# AUTOPILOT_IO.net
KiCad netlist of a schematic drawn in EAGLE
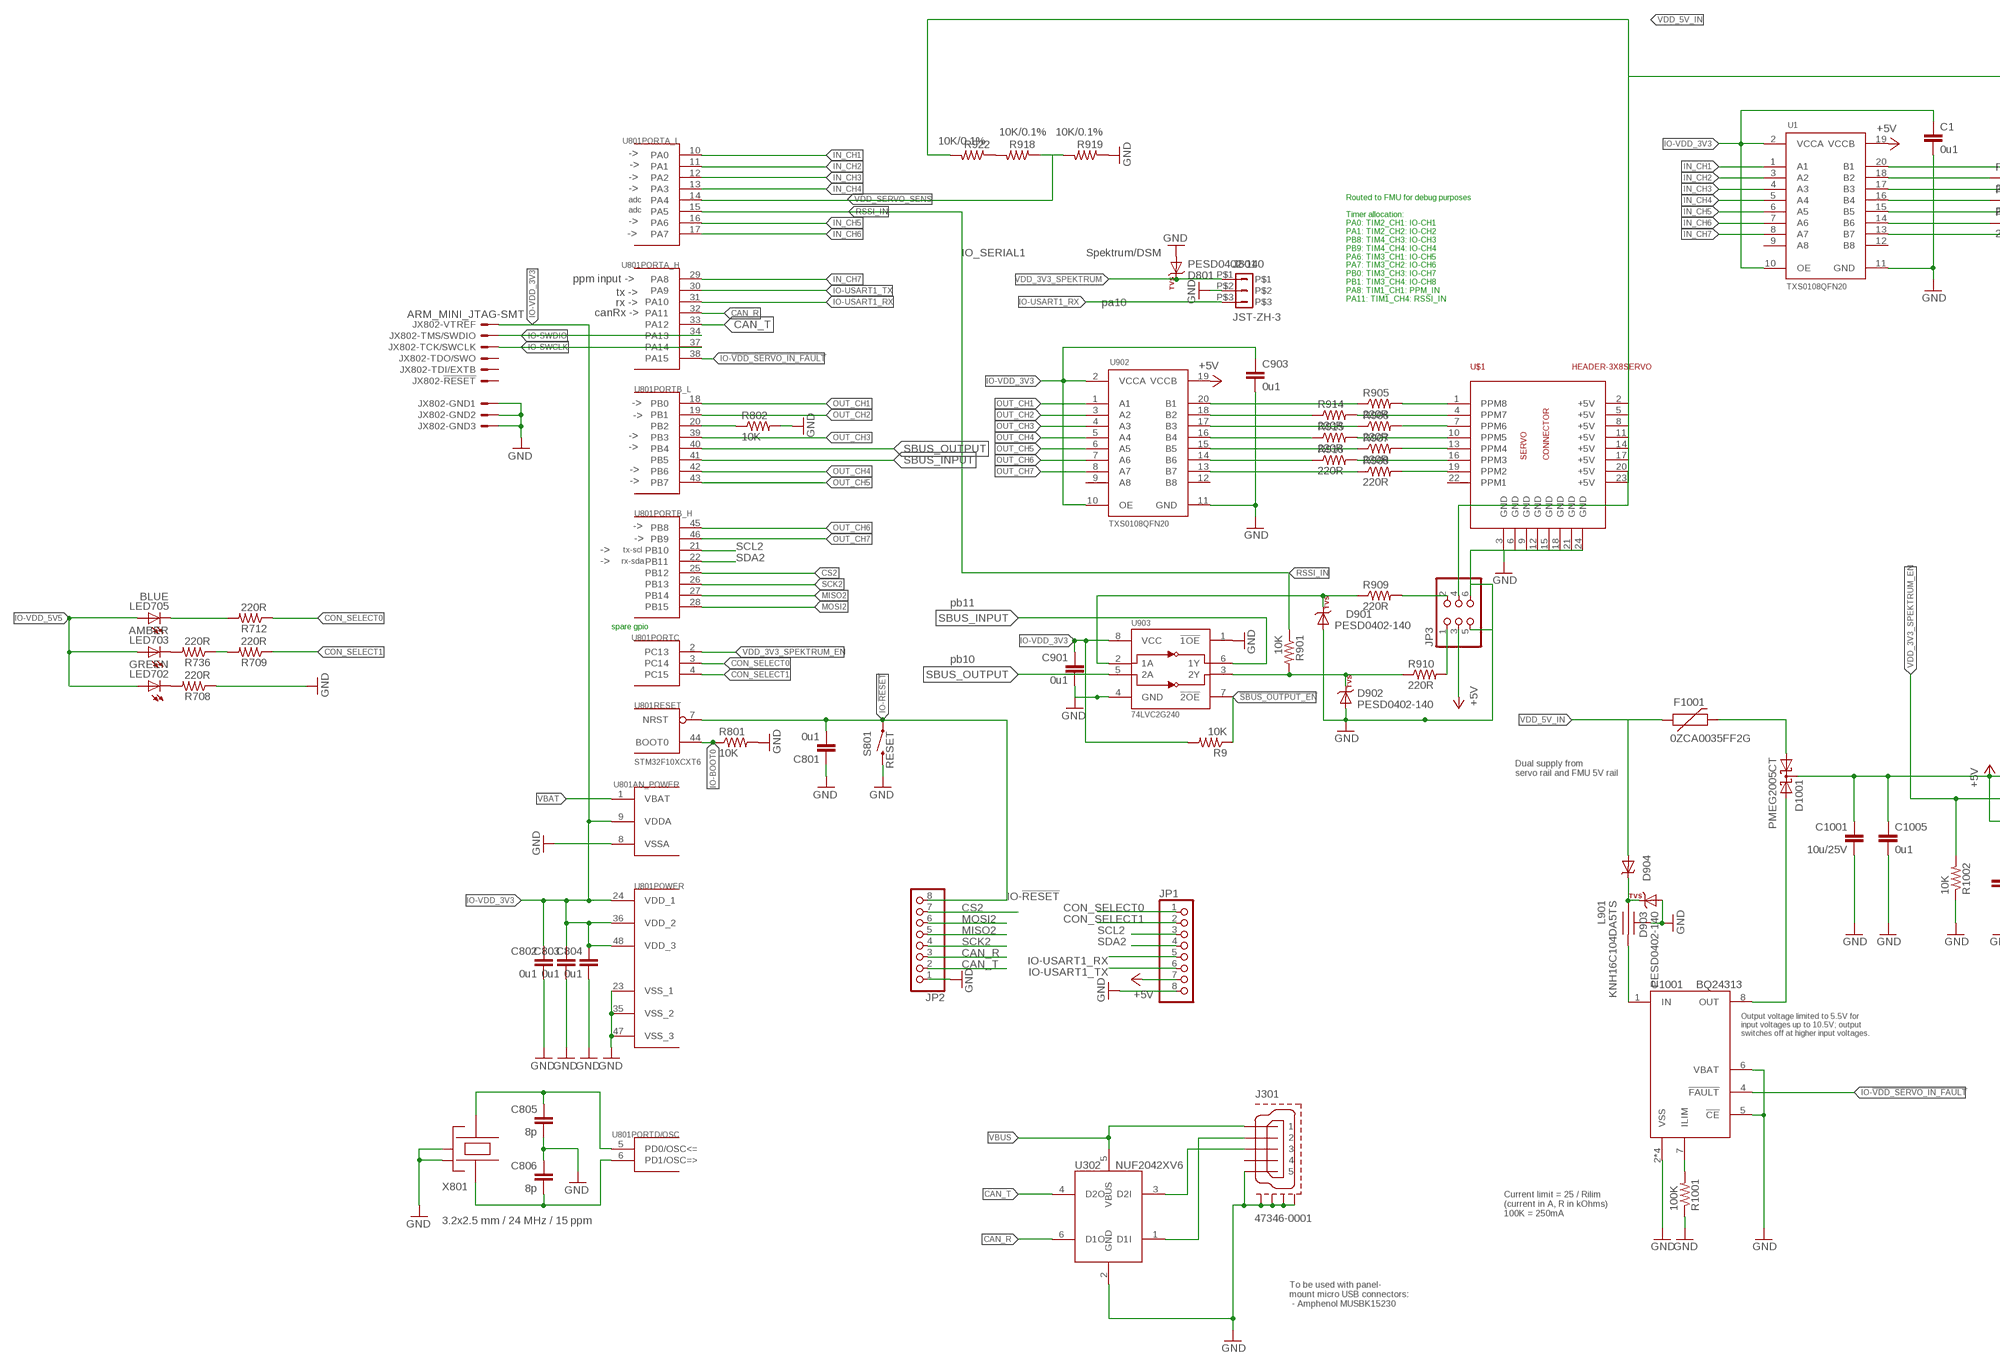
[diagram p0: schematic, sheet 1, part 1 of 2]
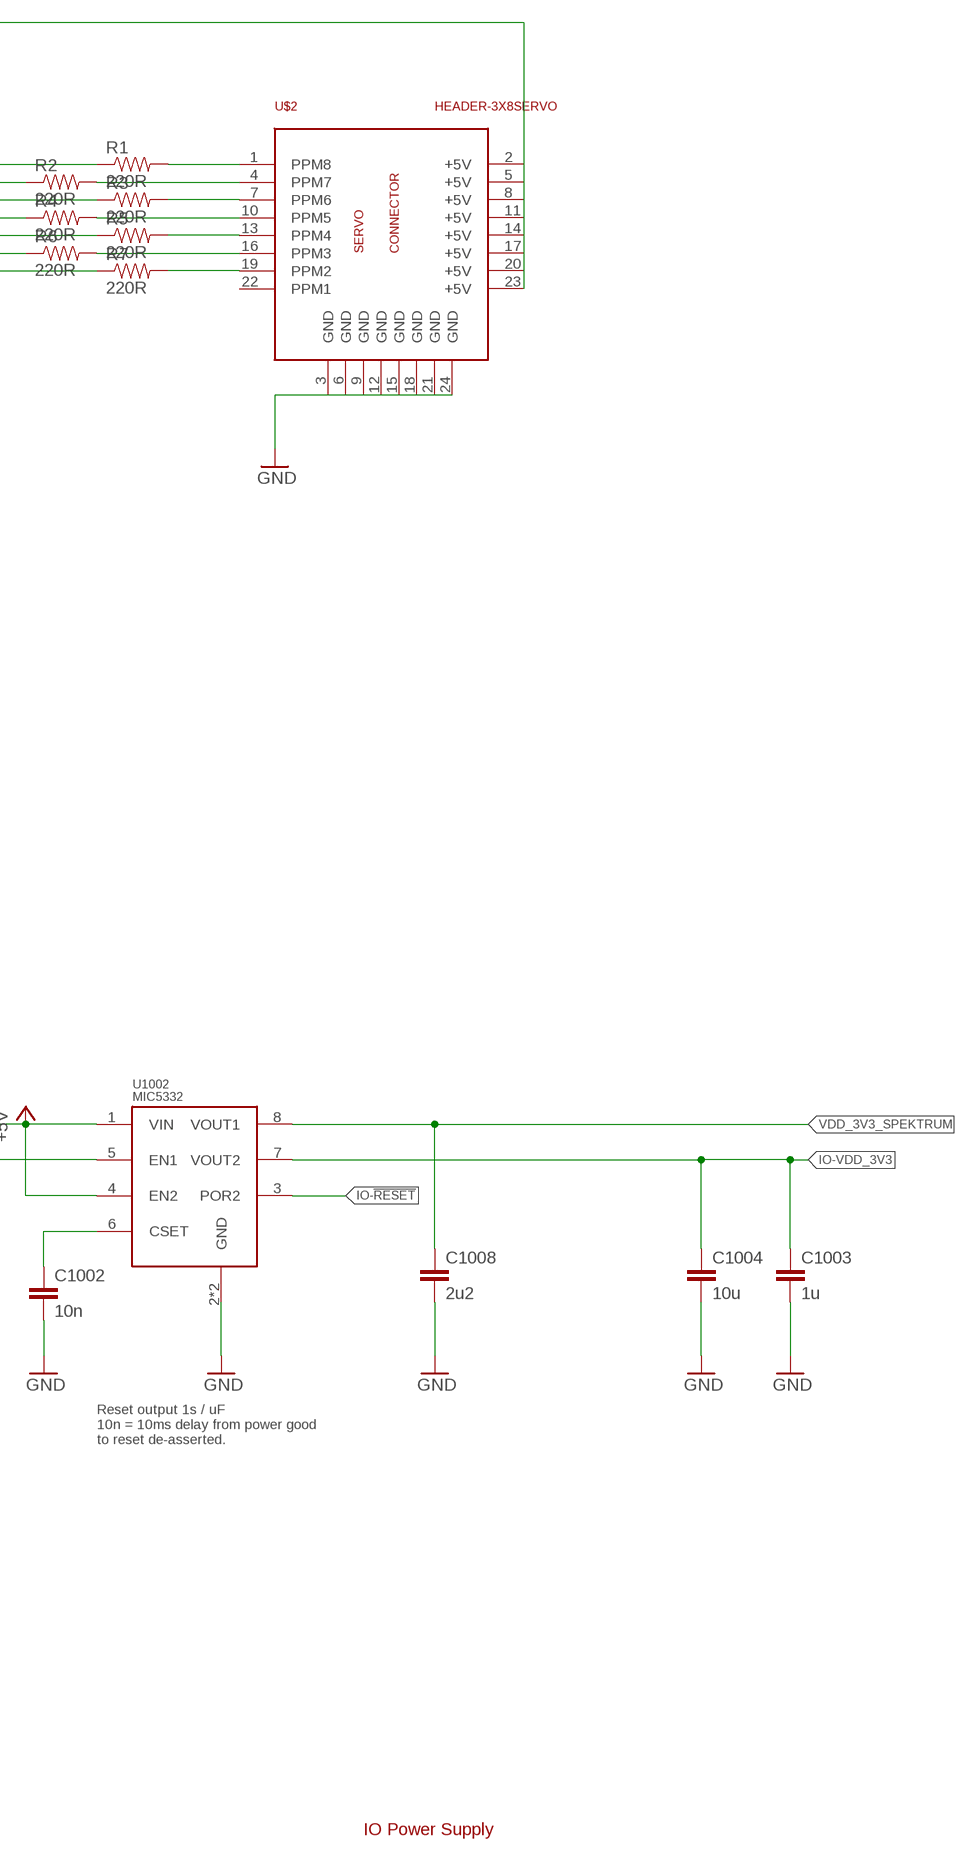
[diagram p1: schematic, sheet 1, part 2 of 2]

(export (version "E")
  (design (tool "Eeschema 10.0.6"))
  (components
    (comp (ref "C1")
      (value "0u1")
      (footprint "eagle-import:0402-CAP")
      (fields (field (name "PARTNO") "CC0402ZRY5V7BB104"))
      (libsource (lib "eagle-import") (part "CAP0402"))
    )
    (comp (ref "C801")
      (value "0u1")
      (footprint "eagle-import:0402-CAP")
      (fields (field (name "PARTNO") "CC0402ZRY5V7BB104"))
      (libsource (lib "eagle-import") (part "CAP0402"))
    )
    (comp (ref "C802")
      (value "0u1")
      (footprint "eagle-import:0402-CAP")
      (fields (field (name "PARTNO") "CC0402ZRY5V7BB104"))
      (libsource (lib "eagle-import") (part "CAP0402"))
    )
    (comp (ref "C803")
      (value "0u1")
      (footprint "eagle-import:0402-CAP")
      (fields (field (name "PARTNO") "CC0402ZRY5V7BB104"))
      (libsource (lib "eagle-import") (part "CAP0402"))
    )
    (comp (ref "C804")
      (value "0u1")
      (footprint "eagle-import:0402-CAP")
      (fields (field (name "PARTNO") "CC0402ZRY5V7BB104"))
      (libsource (lib "eagle-import") (part "CAP0402"))
    )
    (comp (ref "C805")
      (value "8p")
      (footprint "eagle-import:0402-CAP")
      (fields (field (name "PARTNO") "C1005C0G1H080C"))
      (libsource (lib "eagle-import") (part "CAP0402"))
    )
    (comp (ref "C806")
      (value "8p")
      (footprint "eagle-import:0402-CAP")
      (fields (field (name "PARTNO") "C1005C0G1H080C"))
      (libsource (lib "eagle-import") (part "CAP0402"))
    )
    (comp (ref "C901")
      (value "0u1")
      (footprint "eagle-import:0402-CAP")
      (fields (field (name "PARTNO") "CC0402ZRY5V7BB104"))
      (libsource (lib "eagle-import") (part "CAP0402"))
    )
    (comp (ref "C903")
      (value "0u1")
      (footprint "eagle-import:0402-CAP")
      (fields (field (name "PARTNO") "CC0402ZRY5V7BB104"))
      (libsource (lib "eagle-import") (part "CAP0402"))
    )
    (comp (ref "C1001")
      (value "10u/25V")
      (footprint "eagle-import:0805-CAP")
      (fields (field (name "PARTNO") "CL21A106KAYNNNE"))
      (libsource (lib "eagle-import") (part "CAP0805"))
    )
    (comp (ref "C1002")
      (value "10n")
      (footprint "eagle-import:0402-CAP")
      (fields (field (name "PARTNO") "CC0402KRX7R7BB103"))
      (libsource (lib "eagle-import") (part "CAP0402"))
    )
    (comp (ref "C1003")
      (value "1u")
      (footprint "eagle-import:0603-CAP")
      (fields (field (name "PARTNO") "CC0603ZRY5V7BB105"))
      (libsource (lib "eagle-import") (part "CAP0603"))
    )
    (comp (ref "C1004")
      (value "10u")
      (footprint "eagle-import:0603-CAP")
      (fields (field (name "PARTNO") "C1608X5R1A106K080AC"))
      (libsource (lib "eagle-import") (part "CAP0603"))
    )
    (comp (ref "C1005")
      (value "0u1")
      (footprint "eagle-import:0402-CAP")
      (fields (field (name "PARTNO") "CC0402ZRY5V7BB104"))
      (libsource (lib "eagle-import") (part "CAP0402"))
    )
    (comp (ref "C1008")
      (value "2u2")
      (footprint "eagle-import:0402-CAP")
      (fields (field (name "PARTNO") "C1005X6S1C225K050BC"))
      (libsource (lib "eagle-import") (part "CAP0402"))
    )
    (comp (ref "D801")
      (value "PESD0402-140")
      (footprint "eagle-import:0402-TVS")
      (libsource (lib "eagle-import") (part "DIODE-TVS"))
    )
    (comp (ref "D901")
      (value "PESD0402-140")
      (footprint "eagle-import:0402-TVS")
      (libsource (lib "eagle-import") (part "DIODE-TVS"))
    )
    (comp (ref "D902")
      (value "PESD0402-140")
      (footprint "eagle-import:0402-TVS")
      (libsource (lib "eagle-import") (part "DIODE-TVS"))
    )
    (comp (ref "D903")
      (value "PESD0402-140")
      (footprint "eagle-import:0402-TVS")
      (libsource (lib "eagle-import") (part "DIODE-TVS"))
    )
    (comp (ref "D904")
      (value "MSS1P4-M3")
      (footprint "eagle-import:MICROSMP")
      (fields (field (name "PARTNO") "MSS1P4-M3/89A"))
      (libsource (lib "eagle-import") (part "DIODE-SCHOTTKY_MSMP"))
    )
    (comp (ref "D1001")
      (value "PMEG2005CT")
      (footprint "eagle-import:SOT23-3")
      (libsource (lib "eagle-import") (part "PMEG2005CT"))
    )
    (comp (ref "F1001")
      (value "0ZCA0035FF2G")
      (footprint "eagle-import:PTC-1206")
      (libsource (lib "eagle-import") (part "PTCSMD"))
    )
    (comp (ref "J301")
      (value "47346-0001")
      (footprint "eagle-import:MOLEX-47346-0001")
      (libsource (lib "eagle-import") (part "MOLEX-47346-0001"))
    )
    (comp (ref "J801")
      (value "JST-ZH-3")
      (footprint "eagle-import:JST-ZH-SMT-VERTICAL")
      (fields (field (name "PARTNO") "B3B-ZR-SM4-TF (LF)(SN)(P)"))
      (libsource (lib "eagle-import") (part "JST-ZH-3"))
    )
    (comp (ref "JP1")
      (value "PINHD-1X8")
      (footprint "eagle-import:1X08")
      (libsource (lib "eagle-import") (part "PINHD-1X8"))
    )
    (comp (ref "JP2")
      (value "PINHD-1X8")
      (footprint "eagle-import:1X08")
      (libsource (lib "eagle-import") (part "PINHD-1X8"))
    )
    (comp (ref "JP3")
      (value "PINHD-2X3")
      (footprint "eagle-import:2X03")
      (libsource (lib "eagle-import") (part "PINHD-2X3"))
    )
    (comp (ref "JX802")
      (value "ARM_MINI_JTAG-SMT")
      (footprint "eagle-import:FTSH-105-01-XXX-DV-K")
      (fields (field (name "BOM") "EXCLUDE") (field (name "PARTNO") "M50-3900542"))
      (libsource (lib "eagle-import") (part "ARM_MINI_JTAG-SMT"))
    )
    (comp (ref "L901")
      (value "KNH16C104DA5TS")
      (footprint "eagle-import:KYOCERA-KNH16-DA")
      (libsource (lib "eagle-import") (part "KNH16C104DA5TS"))
    )
    (comp (ref "LED702")
      (value "GREEN")
      (footprint "eagle-import:0603-LED")
      (fields (field (name "PARTNO") "APTD1608CGCK"))
      (libsource (lib "eagle-import") (part "LED0603"))
    )
    (comp (ref "LED703")
      (value "AMBER")
      (footprint "eagle-import:0603-LED")
      (fields (field (name "PARTNO") "APTD1608SECK"))
      (libsource (lib "eagle-import") (part "LED0603"))
    )
    (comp (ref "LED705")
      (value "BLUE")
      (footprint "eagle-import:0603-LED")
      (fields (field (name "PARTNO") "APTD1608QBC/D"))
      (libsource (lib "eagle-import") (part "LED0603"))
    )
    (comp (ref "R1")
      (value "220R")
      (footprint "eagle-import:0402-RES")
      (fields (field (name "PARTNO") "RC0402FR-07220RL"))
      (libsource (lib "eagle-import") (part "RESISTOR0402-RES"))
    )
    (comp (ref "R2")
      (value "220R")
      (footprint "eagle-import:0402-RES")
      (fields (field (name "PARTNO") "RC0402FR-07220RL"))
      (libsource (lib "eagle-import") (part "RESISTOR0402-RES"))
    )
    (comp (ref "R3")
      (value "220R")
      (footprint "eagle-import:0402-RES")
      (fields (field (name "PARTNO") "RC0402FR-07220RL"))
      (libsource (lib "eagle-import") (part "RESISTOR0402-RES"))
    )
    (comp (ref "R4")
      (value "220R")
      (footprint "eagle-import:0402-RES")
      (fields (field (name "PARTNO") "RC0402FR-07220RL"))
      (libsource (lib "eagle-import") (part "RESISTOR0402-RES"))
    )
    (comp (ref "R5")
      (value "220R")
      (footprint "eagle-import:0402-RES")
      (fields (field (name "PARTNO") "RC0402FR-07220RL"))
      (libsource (lib "eagle-import") (part "RESISTOR0402-RES"))
    )
    (comp (ref "R6")
      (value "220R")
      (footprint "eagle-import:0402-RES")
      (fields (field (name "PARTNO") "RC0402FR-07220RL"))
      (libsource (lib "eagle-import") (part "RESISTOR0402-RES"))
    )
    (comp (ref "R7")
      (value "220R")
      (footprint "eagle-import:0402-RES")
      (fields (field (name "PARTNO") "RC0402FR-07220RL"))
      (libsource (lib "eagle-import") (part "RESISTOR0402-RES"))
    )
    (comp (ref "R9")
      (value "10K")
      (footprint "eagle-import:0402-RES")
      (fields (field (name "PARTNO") "RC0402FR-0710KL"))
      (libsource (lib "eagle-import") (part "RESISTOR0402-RES"))
    )
    (comp (ref "R708")
      (value "220R")
      (footprint "eagle-import:0402-RES")
      (fields (field (name "PARTNO") "RC0402FR-07220RL"))
      (libsource (lib "eagle-import") (part "RESISTOR0402-RES"))
    )
    (comp (ref "R709")
      (value "220R")
      (footprint "eagle-import:0402-RES")
      (fields (field (name "PARTNO") "RC0402FR-07220RL"))
      (libsource (lib "eagle-import") (part "RESISTOR0402-RES"))
    )
    (comp (ref "R712")
      (value "220R")
      (footprint "eagle-import:0402-RES")
      (fields (field (name "PARTNO") "RC0402FR-07220RL"))
      (libsource (lib "eagle-import") (part "RESISTOR0402-RES"))
    )
    (comp (ref "R736")
      (value "220R")
      (footprint "eagle-import:0402-RES")
      (fields (field (name "PARTNO") "RC0402FR-07220RL"))
      (libsource (lib "eagle-import") (part "RESISTOR0402-RES"))
    )
    (comp (ref "R801")
      (value "10K")
      (footprint "eagle-import:0402-RES")
      (fields (field (name "PARTNO") "RC0402FR-0710KL"))
      (libsource (lib "eagle-import") (part "RESISTOR0402-RES"))
    )
    (comp (ref "R802")
      (value "10K")
      (footprint "eagle-import:0402-RES")
      (fields (field (name "PARTNO") "RC0402FR-0710KL"))
      (libsource (lib "eagle-import") (part "RESISTOR0402-RES"))
    )
    (comp (ref "R901")
      (value "10K")
      (footprint "eagle-import:0402-RES")
      (fields (field (name "PARTNO") "RC0402FR-0710KL"))
      (libsource (lib "eagle-import") (part "RESISTOR0402-RES"))
    )
    (comp (ref "R905")
      (value "220R")
      (footprint "eagle-import:0402-RES")
      (fields (field (name "PARTNO") "RC0402FR-07220RL"))
      (libsource (lib "eagle-import") (part "RESISTOR0402-RES"))
    )
    (comp (ref "R906")
      (value "220R")
      (footprint "eagle-import:0402-RES")
      (fields (field (name "PARTNO") "RC0402FR-07220RL"))
      (libsource (lib "eagle-import") (part "RESISTOR0402-RES"))
    )
    (comp (ref "R907")
      (value "220R")
      (footprint "eagle-import:0402-RES")
      (fields (field (name "PARTNO") "RC0402FR-07220RL"))
      (libsource (lib "eagle-import") (part "RESISTOR0402-RES"))
    )
    (comp (ref "R908")
      (value "220R")
      (footprint "eagle-import:0402-RES")
      (fields (field (name "PARTNO") "RC0402FR-07220RL"))
      (libsource (lib "eagle-import") (part "RESISTOR0402-RES"))
    )
    (comp (ref "R909")
      (value "220R")
      (footprint "eagle-import:0402-RES")
      (fields (field (name "PARTNO") "RC0402FR-07220RL"))
      (libsource (lib "eagle-import") (part "RESISTOR0402-RES"))
    )
    (comp (ref "R910")
      (value "220R")
      (footprint "eagle-import:0402-RES")
      (fields (field (name "PARTNO") "RC0402FR-07220RL"))
      (libsource (lib "eagle-import") (part "RESISTOR0402-RES"))
    )
    (comp (ref "R914")
      (value "220R")
      (footprint "eagle-import:0402-RES")
      (fields (field (name "PARTNO") "RC0402FR-07220RL"))
      (libsource (lib "eagle-import") (part "RESISTOR0402-RES"))
    )
    (comp (ref "R915")
      (value "220R")
      (footprint "eagle-import:0402-RES")
      (fields (field (name "PARTNO") "RC0402FR-07220RL"))
      (libsource (lib "eagle-import") (part "RESISTOR0402-RES"))
    )
    (comp (ref "R916")
      (value "220R")
      (footprint "eagle-import:0402-RES")
      (fields (field (name "PARTNO") "RC0402FR-07220RL"))
      (libsource (lib "eagle-import") (part "RESISTOR0402-RES"))
    )
    (comp (ref "R918")
      (value "10K/0.1%")
      (footprint "eagle-import:0402-RES")
      (fields (field (name "PARTNO") "ERA-2AEB103X"))
      (libsource (lib "eagle-import") (part "RESISTOR0402-RES"))
    )
    (comp (ref "R919")
      (value "10K/0.1%")
      (footprint "eagle-import:0402-RES")
      (fields (field (name "PARTNO") "ERA-2AEB103X"))
      (libsource (lib "eagle-import") (part "RESISTOR0402-RES"))
    )
    (comp (ref "R922")
      (value "10K/0.1%")
      (footprint "eagle-import:0402-RES")
      (fields (field (name "PARTNO") "ERA-2AEB103X"))
      (libsource (lib "eagle-import") (part "RESISTOR0402-RES"))
    )
    (comp (ref "R1001")
      (value "100K")
      (footprint "eagle-import:0402-RES")
      (fields (field (name "PARTNO") "RC0402FR-07100KL"))
      (libsource (lib "eagle-import") (part "RESISTOR0402-RES"))
    )
    (comp (ref "R1002")
      (value "10K")
      (footprint "eagle-import:0402-RES")
      (fields (field (name "PARTNO") "RC0402FR-0710KL"))
      (libsource (lib "eagle-import") (part "RESISTOR0402-RES"))
    )
    (comp (ref "S801")
      (value "RESET")
      (footprint "eagle-import:EVQP7J01K")
      (fields (field (name "PARTNO") "EVQ-P7J01P"))
      (libsource (lib "eagle-import") (part "SWITCH-MOMENTARY-2"))
    )
    (comp (ref "U$1")
      (value "HEADER-3X8SERVO")
      (footprint "eagle-import:3X8RA")
      (libsource (lib "eagle-import") (part "HEADER-3X8SERVO"))
    )
    (comp (ref "U$2")
      (value "HEADER-3X8SERVO")
      (footprint "eagle-import:3X8RA")
      (libsource (lib "eagle-import") (part "HEADER-3X8SERVO"))
    )
    (comp (ref "U1")
      (value "TXS0108QFN20")
      (footprint "eagle-import:QFN20-RGY")
      (fields (field (name "PARTNO") "TXS0108ERGYR"))
      (libsource (lib "eagle-import") (part "TXS0108QFN20"))
    )
    (comp (ref "U302")
      (value "NUF2042XV6")
      (footprint "eagle-import:SOT563-6")
      (fields (field (name "PARTNO") "NUF2042XV6T1G"))
      (libsource (lib "eagle-import") (part "NUF2042XV6"))
    )
    (comp (ref "U801")
      (value "STM32F10XCXT6")
      (footprint "eagle-import:TQFP48")
      (fields (field (name "PARTNO") "STM32F100C8T6B"))
      (libsource (lib "eagle-import") (part "STM32F10XCXT6"))
    )
    (comp (ref "U902")
      (value "TXS0108QFN20")
      (footprint "eagle-import:QFN20-RGY")
      (fields (field (name "PARTNO") "TXS0108ERGYR"))
      (libsource (lib "eagle-import") (part "TXS0108QFN20"))
    )
    (comp (ref "U903")
      (value "74LVC2G240")
      (footprint "eagle-import:TSSOP8_SOT505-2")
      (fields (field (name "PARTNO") "74LVC2G240DP,125"))
      (libsource (lib "eagle-import") (part "74LVC2G240-TSSOP-8"))
    )
    (comp (ref "U1001")
      (value "BQ24313")
      (footprint "eagle-import:QFN8-DSG")
      (fields (field (name "PARTNO") "BQ24313DSGT"))
      (libsource (lib "eagle-import") (part "BQ24313"))
    )
    (comp (ref "U1002")
      (value "MIC5332")
      (footprint "eagle-import:MLF-8-EPAD")
      (fields (field (name "PARTNO") "MIC5332-SSYMT"))
      (libsource (lib "eagle-import") (part "MIC5332"))
    )
    (comp (ref "X801")
      (value "3.2x2.5 mm / 24 MHz / 15 ppm")
      (footprint "eagle-import:OSCILLATOR-3.2X2.5")
      (fields (field (name "PARTNO") "NX3225SA-24.000000MHZ"))
      (libsource (lib "eagle-import") (part "OSCILLATOR-3.2X2.5"))
    )
  )
  (nets
    (net (code "1") (name "+5V") (class "Default")
      (node (ref "C1001") (pin "P$1") (pinfunction "1_P$1") (pintype "passive"))
      (node (ref "C1005") (pin "P$1") (pinfunction "1_P$1") (pintype "passive"))
      (node (ref "D1001") (pin "3") (pinfunction "CC_3") (pintype "passive"))
      (node (ref "JP1") (pin "7") (pinfunction "7_7") (pintype "passive"))
      (node (ref "JP3") (pin "3") (pinfunction "3_3") (pintype "passive"))
      (node (ref "U1") (pin "19") (pinfunction "VCCB_19") (pintype "input"))
      (node (ref "U1002") (pin "1") (pinfunction "VIN_1") (pintype "bidirectional"))
      (node (ref "U1002") (pin "4") (pinfunction "EN2_4") (pintype "bidirectional"))
      (node (ref "U902") (pin "19") (pinfunction "VCCB_19") (pintype "input"))
    )
    (net (code "2") (name "/IO-~{RESET}") (class "Default")
      (node (ref "C801") (pin "P$2") (pinfunction "2_P$2") (pintype "passive"))
      (node (ref "JP2") (pin "8") (pinfunction "8_8") (pintype "passive"))
      (node (ref "S801") (pin "A1") (pinfunction "1_A1") (pintype "passive"))
      (node (ref "U1002") (pin "3") (pinfunction "POR2_3") (pintype "bidirectional"))
      (node (ref "U801") (pin "7") (pinfunction "NRST_7") (pintype "input"))
    )
    (net (code "3") (name "/IO-~{VDD_SERVO_IN_FAULT}") (class "Default")
      (node (ref "U1001") (pin "4") (pinfunction "~{FAULT}_4") (pintype "bidirectional"))
      (node (ref "U801") (pin "38") (pinfunction "PA15_38") (pintype "bidirectional"))
    )
    (net (code "4") (name "/SCL2") (class "Default")
      (node (ref "JP1") (pin "3") (pinfunction "3_3") (pintype "passive"))
      (node (ref "U801") (pin "21") (pinfunction "PB10_21") (pintype "bidirectional"))
    )
    (net (code "5") (name "/SDA2") (class "Default")
      (node (ref "JP1") (pin "4") (pinfunction "4_4") (pintype "passive"))
      (node (ref "U801") (pin "22") (pinfunction "PB11_22") (pintype "bidirectional"))
    )
    (net (code "6") (name "/~{SBUS_OUTPUT_EN}") (class "Default")
      (node (ref "R9") (pin "P$1") (pinfunction "1_P$1") (pintype "passive"))
      (node (ref "U903") (pin "7") (pinfunction "~{2OE}_7") (pintype "input"))
    )
    (net (code "7") (name "CAN_R") (class "Default")
      (node (ref "JP2") (pin "3") (pinfunction "3_3") (pintype "passive"))
      (node (ref "U302") (pin "6") (pinfunction "D1O_6") (pintype "bidirectional"))
      (node (ref "U801") (pin "32") (pinfunction "PA11_32") (pintype "bidirectional"))
    )
    (net (code "8") (name "CAN_T") (class "Default")
      (node (ref "JP2") (pin "2") (pinfunction "2_2") (pintype "passive"))
      (node (ref "U302") (pin "4") (pinfunction "D2O_4") (pintype "bidirectional"))
      (node (ref "U801") (pin "33") (pinfunction "PA12_33") (pintype "bidirectional"))
    )
    (net (code "9") (name "CON_SELECT0") (class "Default")
      (node (ref "JP1") (pin "1") (pinfunction "1_1") (pintype "passive"))
      (node (ref "R712") (pin "P$1") (pinfunction "1_P$1") (pintype "passive"))
      (node (ref "U801") (pin "3") (pinfunction "PC14_3") (pintype "bidirectional"))
    )
    (net (code "10") (name "CON_SELECT1") (class "Default")
      (node (ref "JP1") (pin "2") (pinfunction "2_2") (pintype "passive"))
      (node (ref "R709") (pin "P$1") (pinfunction "1_P$1") (pintype "passive"))
      (node (ref "U801") (pin "4") (pinfunction "PC15_4") (pintype "bidirectional"))
    )
    (net (code "11") (name "CS2") (class "Default")
      (node (ref "JP2") (pin "7") (pinfunction "7_7") (pintype "passive"))
      (node (ref "U801") (pin "25") (pinfunction "PB12_25") (pintype "bidirectional"))
    )
    (net (code "12") (name "GND") (class "Default")
      (node (ref "C1") (pin "P$2") (pinfunction "2_P$2") (pintype "passive"))
      (node (ref "C1001") (pin "P$2") (pinfunction "2_P$2") (pintype "passive"))
      (node (ref "C1002") (pin "P$2") (pinfunction "2_P$2") (pintype "passive"))
      (node (ref "C1003") (pin "P$2") (pinfunction "2_P$2") (pintype "passive"))
      (node (ref "C1004") (pin "P$2") (pinfunction "2_P$2") (pintype "passive"))
      (node (ref "C1005") (pin "P$2") (pinfunction "2_P$2") (pintype "passive"))
      (node (ref "C1008") (pin "P$2") (pinfunction "2_P$2") (pintype "passive"))
      (node (ref "C801") (pin "P$1") (pinfunction "1_P$1") (pintype "passive"))
      (node (ref "C802") (pin "P$2") (pinfunction "2_P$2") (pintype "passive"))
      (node (ref "C803") (pin "P$2") (pinfunction "2_P$2") (pintype "passive"))
      (node (ref "C804") (pin "P$2") (pinfunction "2_P$2") (pintype "passive"))
      (node (ref "C805") (pin "P$2") (pinfunction "2_P$2") (pintype "passive"))
      (node (ref "C806") (pin "P$1") (pinfunction "1_P$1") (pintype "passive"))
      (node (ref "C901") (pin "P$2") (pinfunction "2_P$2") (pintype "passive"))
      (node (ref "C903") (pin "P$2") (pinfunction "2_P$2") (pintype "passive"))
      (node (ref "D801") (pin "A") (pinfunction "A_A") (pintype "passive"))
      (node (ref "D901") (pin "A") (pinfunction "A_A") (pintype "passive"))
      (node (ref "D902") (pin "A") (pinfunction "A_A") (pintype "passive"))
      (node (ref "D903") (pin "A") (pinfunction "A_A") (pintype "passive"))
      (node (ref "J301") (pin "GND") (pinfunction "5_GND") (pintype "power_in"))
      (node (ref "J301") (pin "GND1") (pinfunction "GND1_GND1") (pintype "bidirectional"))
      (node (ref "J301") (pin "GND2") (pinfunction "GND2_GND2") (pintype "bidirectional"))
      (node (ref "J301") (pin "GND3") (pinfunction "GND3_GND3") (pintype "bidirectional"))
      (node (ref "J301") (pin "GND4") (pinfunction "GND4_GND4") (pintype "bidirectional"))
      (node (ref "J801") (pin "P$2") (pinfunction "P$2_P$2") (pintype "bidirectional"))
      (node (ref "JP1") (pin "8") (pinfunction "8_8") (pintype "passive"))
      (node (ref "JP2") (pin "1") (pinfunction "1_1") (pintype "passive"))
      (node (ref "JP3") (pin "5") (pinfunction "5_5") (pintype "passive"))
      (node (ref "JP3") (pin "6") (pinfunction "6_6") (pintype "passive"))
      (node (ref "JX802") (pin "3") (pinfunction "S_3") (pintype "passive"))
      (node (ref "JX802") (pin "5") (pinfunction "S_5") (pintype "passive"))
      (node (ref "JX802") (pin "9") (pinfunction "S_9") (pintype "passive"))
      (node (ref "L901") (pin "P$3") (pinfunction "P$3_P$3") (pintype "bidirectional"))
      (node (ref "L901") (pin "P$4") (pinfunction "P$3_P$4") (pintype "bidirectional"))
      (node (ref "L901") (pin "P$5") (pinfunction "P$3_P$5") (pintype "bidirectional"))
      (node (ref "R1001") (pin "P$1") (pinfunction "1_P$1") (pintype "passive"))
      (node (ref "R1002") (pin "P$1") (pinfunction "1_P$1") (pintype "passive"))
      (node (ref "R708") (pin "P$1") (pinfunction "1_P$1") (pintype "passive"))
      (node (ref "R801") (pin "P$2") (pinfunction "2_P$2") (pintype "passive"))
      (node (ref "R802") (pin "P$2") (pinfunction "2_P$2") (pintype "passive"))
      (node (ref "R919") (pin "P$1") (pinfunction "1_P$1") (pintype "passive"))
      (node (ref "S801") (pin "B3") (pinfunction "2_B3") (pintype "passive"))
      (node (ref "U$1") (pin "12") (pinfunction "GND_12") (pintype "bidirectional"))
      (node (ref "U$1") (pin "15") (pinfunction "GND_15") (pintype "bidirectional"))
      (node (ref "U$1") (pin "18") (pinfunction "GND_18") (pintype "bidirectional"))
      (node (ref "U$1") (pin "21") (pinfunction "GND_21") (pintype "bidirectional"))
      (node (ref "U$1") (pin "24") (pinfunction "GND_24") (pintype "bidirectional"))
      (node (ref "U$1") (pin "3") (pinfunction "GND_3") (pintype "bidirectional"))
      (node (ref "U$1") (pin "6") (pinfunction "GND_6") (pintype "bidirectional"))
      (node (ref "U$1") (pin "9") (pinfunction "GND_9") (pintype "bidirectional"))
      (node (ref "U$2") (pin "12") (pinfunction "GND_12") (pintype "bidirectional"))
      (node (ref "U$2") (pin "15") (pinfunction "GND_15") (pintype "bidirectional"))
      (node (ref "U$2") (pin "18") (pinfunction "GND_18") (pintype "bidirectional"))
      (node (ref "U$2") (pin "21") (pinfunction "GND_21") (pintype "bidirectional"))
      (node (ref "U$2") (pin "24") (pinfunction "GND_24") (pintype "bidirectional"))
      (node (ref "U$2") (pin "3") (pinfunction "GND_3") (pintype "bidirectional"))
      (node (ref "U$2") (pin "6") (pinfunction "GND_6") (pintype "bidirectional"))
      (node (ref "U$2") (pin "9") (pinfunction "GND_9") (pintype "bidirectional"))
      (node (ref "U1") (pin "11") (pinfunction "GND_11") (pintype "power_in"))
      (node (ref "U1001") (pin "2") (pinfunction "VSS_2") (pintype "bidirectional"))
      (node (ref "U1001") (pin "5") (pinfunction "~{CE}_5") (pintype "bidirectional"))
      (node (ref "U1001") (pin "6") (pinfunction "VBAT_6") (pintype "bidirectional"))
      (node (ref "U1001") (pin "GND") (pinfunction "VSS_GND") (pintype "bidirectional"))
      (node (ref "U1001") (pin "P$2") (pinfunction "VSS_P$2") (pintype "bidirectional"))
      (node (ref "U1001") (pin "P$3") (pinfunction "VSS_P$3") (pintype "bidirectional"))
      (node (ref "U1002") (pin "2") (pinfunction "GND_2") (pintype "bidirectional"))
      (node (ref "U1002") (pin "GND") (pinfunction "GND_GND") (pintype "bidirectional"))
      (node (ref "U302") (pin "2") (pinfunction "GND_2") (pintype "bidirectional"))
      (node (ref "U801") (pin "23") (pinfunction "VSS_1_23") (pintype "power_in"))
      (node (ref "U801") (pin "35") (pinfunction "VSS_2_35") (pintype "power_in"))
      (node (ref "U801") (pin "47") (pinfunction "VSS_3_47") (pintype "power_in"))
      (node (ref "U801") (pin "8") (pinfunction "VSSA_8") (pintype "power_in"))
      (node (ref "U902") (pin "11") (pinfunction "GND_11") (pintype "power_in"))
      (node (ref "U903") (pin "1") (pinfunction "~{1OE}_1") (pintype "input"))
      (node (ref "U903") (pin "4") (pinfunction "GND_4") (pintype "power_in"))
      (node (ref "X801") (pin "2") (pinfunction "NC_2_2") (pintype "power_in"))
      (node (ref "X801") (pin "4") (pinfunction "NC_4_4") (pintype "power_in"))
    )
    (net (code "13") (name "IN_CH1") (class "Default")
      (node (ref "U1") (pin "1") (pinfunction "A1_1") (pintype "bidirectional"))
      (node (ref "U801") (pin "10") (pinfunction "PA0_10") (pintype "bidirectional"))
    )
    (net (code "14") (name "IN_CH2") (class "Default")
      (node (ref "U1") (pin "3") (pinfunction "A2_3") (pintype "bidirectional"))
      (node (ref "U801") (pin "11") (pinfunction "PA1_11") (pintype "bidirectional"))
    )
    (net (code "15") (name "IN_CH3") (class "Default")
      (node (ref "U1") (pin "4") (pinfunction "A3_4") (pintype "bidirectional"))
      (node (ref "U801") (pin "12") (pinfunction "PA2_12") (pintype "bidirectional"))
    )
    (net (code "16") (name "IN_CH4") (class "Default")
      (node (ref "U1") (pin "5") (pinfunction "A4_5") (pintype "bidirectional"))
      (node (ref "U801") (pin "13") (pinfunction "PA3_13") (pintype "bidirectional"))
    )
    (net (code "17") (name "IN_CH5") (class "Default")
      (node (ref "U1") (pin "6") (pinfunction "A5_6") (pintype "bidirectional"))
      (node (ref "U801") (pin "16") (pinfunction "PA6_16") (pintype "bidirectional"))
    )
    (net (code "18") (name "IN_CH6") (class "Default")
      (node (ref "U1") (pin "7") (pinfunction "A6_7") (pintype "bidirectional"))
      (node (ref "U801") (pin "17") (pinfunction "PA7_17") (pintype "bidirectional"))
    )
    (net (code "19") (name "IN_CH7") (class "Default")
      (node (ref "D901") (pin "C") (pinfunction "C_C") (pintype "passive"))
      (node (ref "R909") (pin "P$1") (pinfunction "1_P$1") (pintype "passive"))
      (node (ref "U1") (pin "8") (pinfunction "A7_8") (pintype "bidirectional"))
      (node (ref "U801") (pin "29") (pinfunction "PA8_29") (pintype "bidirectional"))
      (node (ref "U903") (pin "2") (pinfunction "1A_2") (pintype "bidirectional"))
    )
    (net (code "20") (name "IO-BOOT0") (class "Default")
      (node (ref "R801") (pin "P$1") (pinfunction "1_P$1") (pintype "passive"))
      (node (ref "U801") (pin "44") (pinfunction "BOOT0_44") (pintype "input"))
    )
    (net (code "21") (name "IO-SWCLK") (class "Default")
      (node (ref "JX802") (pin "4") (pinfunction "S_4") (pintype "passive"))
      (node (ref "U801") (pin "37") (pinfunction "PA14_37") (pintype "bidirectional"))
    )
    (net (code "22") (name "IO-SWDIO") (class "Default")
      (node (ref "JX802") (pin "2") (pinfunction "S_2") (pintype "passive"))
      (node (ref "U801") (pin "34") (pinfunction "PA13_34") (pintype "bidirectional"))
    )
    (net (code "23") (name "IO-USART1_RX") (class "Default")
      (node (ref "J801") (pin "P$3") (pinfunction "P$3_P$3") (pintype "bidirectional"))
      (node (ref "JP1") (pin "5") (pinfunction "5_5") (pintype "passive"))
      (node (ref "U801") (pin "31") (pinfunction "PA10_31") (pintype "bidirectional"))
    )
    (net (code "24") (name "IO-USART1_TX") (class "Default")
      (node (ref "JP1") (pin "6") (pinfunction "6_6") (pintype "passive"))
      (node (ref "U801") (pin "30") (pinfunction "PA9_30") (pintype "bidirectional"))
    )
    (net (code "25") (name "IO-VDD_3V3") (class "Default")
      (node (ref "C1") (pin "P$1") (pinfunction "1_P$1") (pintype "passive"))
      (node (ref "C1003") (pin "P$1") (pinfunction "1_P$1") (pintype "passive"))
      (node (ref "C1004") (pin "P$1") (pinfunction "1_P$1") (pintype "passive"))
      (node (ref "C802") (pin "P$1") (pinfunction "1_P$1") (pintype "passive"))
      (node (ref "C803") (pin "P$1") (pinfunction "1_P$1") (pintype "passive"))
      (node (ref "C804") (pin "P$1") (pinfunction "1_P$1") (pintype "passive"))
      (node (ref "C901") (pin "P$1") (pinfunction "1_P$1") (pintype "passive"))
      (node (ref "C903") (pin "P$1") (pinfunction "1_P$1") (pintype "passive"))
      (node (ref "JX802") (pin "1") (pinfunction "S_1") (pintype "passive"))
      (node (ref "R9") (pin "P$2") (pinfunction "2_P$2") (pintype "passive"))
      (node (ref "U1") (pin "10") (pinfunction "OE_10") (pintype "input"))
      (node (ref "U1") (pin "2") (pinfunction "VCCA_2") (pintype "input"))
      (node (ref "U1002") (pin "7") (pinfunction "VOUT2_7") (pintype "bidirectional"))
      (node (ref "U801") (pin "24") (pinfunction "VDD_1_24") (pintype "power_in"))
      (node (ref "U801") (pin "36") (pinfunction "VDD_2_36") (pintype "power_in"))
      (node (ref "U801") (pin "48") (pinfunction "VDD_3_48") (pintype "power_in"))
      (node (ref "U801") (pin "9") (pinfunction "VDDA_9") (pintype "power_in"))
      (node (ref "U902") (pin "10") (pinfunction "OE_10") (pintype "input"))
      (node (ref "U902") (pin "2") (pinfunction "VCCA_2") (pintype "input"))
      (node (ref "U903") (pin "8") (pinfunction "VCC_8") (pintype "power_in"))
    )
    (net (code "26") (name "IO-VDD_5V5") (class "Default")
      (node (ref "LED702") (pin "A") (pinfunction "A_A") (pintype "passive"))
      (node (ref "LED703") (pin "A") (pinfunction "A_A") (pintype "passive"))
      (node (ref "LED705") (pin "A") (pinfunction "A_A") (pintype "passive"))
    )
    (net (code "27") (name "MISO2") (class "Default")
      (node (ref "JP2") (pin "5") (pinfunction "5_5") (pintype "passive"))
      (node (ref "U801") (pin "27") (pinfunction "PB14_27") (pintype "bidirectional"))
    )
    (net (code "28") (name "MOSI2") (class "Default")
      (node (ref "JP2") (pin "6") (pinfunction "6_6") (pintype "passive"))
      (node (ref "U801") (pin "28") (pinfunction "PB15_28") (pintype "bidirectional"))
    )
    (net (code "29") (name "Net-(C805-1)") (class "Default")
      (node (ref "C805") (pin "P$1") (pinfunction "1_P$1") (pintype "passive"))
      (node (ref "U801") (pin "5") (pinfunction "PD0/OSC<=_5") (pintype "bidirectional"))
      (node (ref "X801") (pin "3") (pinfunction "3_3") (pintype "bidirectional"))
    )
    (net (code "30") (name "Net-(C806-2)") (class "Default")
      (node (ref "C806") (pin "P$2") (pinfunction "2_P$2") (pintype "passive"))
      (node (ref "U801") (pin "6") (pinfunction "PD1/OSC=>_6") (pintype "bidirectional"))
      (node (ref "X801") (pin "1") (pinfunction "1_1") (pintype "bidirectional"))
    )
    (net (code "31") (name "Net-(C1002-1)") (class "Default")
      (node (ref "C1002") (pin "P$1") (pinfunction "1_P$1") (pintype "passive"))
      (node (ref "U1002") (pin "6") (pinfunction "CSET_6") (pintype "bidirectional"))
    )
    (net (code "32") (name "Net-(D904-C)") (class "Default")
      (node (ref "D903") (pin "C") (pinfunction "C_C") (pintype "passive"))
      (node (ref "D904") (pin "CATHODE") (pinfunction "C_CATHODE") (pintype "passive"))
      (node (ref "L901") (pin "P$1") (pinfunction "P$1_P$1") (pintype "bidirectional"))
    )
    (net (code "33") (name "Net-(D1001-A1)") (class "Default")
      (node (ref "D1001") (pin "1") (pinfunction "A1_1") (pintype "passive"))
      (node (ref "F1001") (pin "2") (pinfunction "2_2") (pintype "bidirectional"))
    )
    (net (code "34") (name "Net-(D1001-A2)") (class "Default")
      (node (ref "D1001") (pin "2") (pinfunction "A2_2") (pintype "passive"))
      (node (ref "U1001") (pin "8") (pinfunction "OUT_8") (pintype "bidirectional"))
    )
    (net (code "35") (name "Net-(J301-2)") (class "Default")
      (node (ref "J301") (pin "D-") (pinfunction "2_D-") (pintype "bidirectional"))
      (node (ref "U302") (pin "1") (pinfunction "D1I_1") (pintype "bidirectional"))
    )
    (net (code "36") (name "Net-(J301-3)") (class "Default")
      (node (ref "J301") (pin "D+") (pinfunction "3_D+") (pintype "bidirectional"))
      (node (ref "U302") (pin "3") (pinfunction "D2I_3") (pintype "bidirectional"))
    )
    (net (code "37") (name "Net-(R1-1)") (class "Default")
      (node (ref "R1") (pin "P$1") (pinfunction "1_P$1") (pintype "passive"))
      (node (ref "U1") (pin "20") (pinfunction "B1_20") (pintype "bidirectional"))
    )
    (net (code "38") (name "Net-(R1-2)") (class "Default")
      (node (ref "R1") (pin "P$2") (pinfunction "2_P$2") (pintype "passive"))
      (node (ref "U$2") (pin "1") (pinfunction "PPM8_1") (pintype "bidirectional"))
    )
    (net (code "39") (name "Net-(R2-1)") (class "Default")
      (node (ref "R2") (pin "P$1") (pinfunction "1_P$1") (pintype "passive"))
      (node (ref "U1") (pin "18") (pinfunction "B2_18") (pintype "bidirectional"))
    )
    (net (code "40") (name "Net-(R2-2)") (class "Default")
      (node (ref "R2") (pin "P$2") (pinfunction "2_P$2") (pintype "passive"))
      (node (ref "U$2") (pin "4") (pinfunction "PPM7_4") (pintype "bidirectional"))
    )
    (net (code "41") (name "Net-(R3-1)") (class "Default")
      (node (ref "R3") (pin "P$1") (pinfunction "1_P$1") (pintype "passive"))
      (node (ref "U1") (pin "17") (pinfunction "B3_17") (pintype "bidirectional"))
    )
    (net (code "42") (name "Net-(R3-2)") (class "Default")
      (node (ref "R3") (pin "P$2") (pinfunction "2_P$2") (pintype "passive"))
      (node (ref "U$2") (pin "7") (pinfunction "PPM6_7") (pintype "bidirectional"))
    )
    (net (code "43") (name "Net-(R4-1)") (class "Default")
      (node (ref "R4") (pin "P$1") (pinfunction "1_P$1") (pintype "passive"))
      (node (ref "U1") (pin "16") (pinfunction "B4_16") (pintype "bidirectional"))
    )
    (net (code "44") (name "Net-(R4-2)") (class "Default")
      (node (ref "R4") (pin "P$2") (pinfunction "2_P$2") (pintype "passive"))
      (node (ref "U$2") (pin "10") (pinfunction "PPM5_10") (pintype "bidirectional"))
    )
    (net (code "45") (name "Net-(R5-1)") (class "Default")
      (node (ref "R5") (pin "P$1") (pinfunction "1_P$1") (pintype "passive"))
      (node (ref "U1") (pin "15") (pinfunction "B5_15") (pintype "bidirectional"))
    )
    (net (code "46") (name "Net-(R5-2)") (class "Default")
      (node (ref "R5") (pin "P$2") (pinfunction "2_P$2") (pintype "passive"))
      (node (ref "U$2") (pin "13") (pinfunction "PPM4_13") (pintype "bidirectional"))
    )
    (net (code "47") (name "Net-(R6-1)") (class "Default")
      (node (ref "R6") (pin "P$1") (pinfunction "1_P$1") (pintype "passive"))
      (node (ref "U1") (pin "14") (pinfunction "B6_14") (pintype "bidirectional"))
    )
    (net (code "48") (name "Net-(R6-2)") (class "Default")
      (node (ref "R6") (pin "P$2") (pinfunction "2_P$2") (pintype "passive"))
      (node (ref "U$2") (pin "16") (pinfunction "PPM3_16") (pintype "bidirectional"))
    )
    (net (code "49") (name "Net-(R7-1)") (class "Default")
      (node (ref "R7") (pin "P$1") (pinfunction "1_P$1") (pintype "passive"))
      (node (ref "U1") (pin "13") (pinfunction "B7_13") (pintype "bidirectional"))
    )
    (net (code "50") (name "Net-(R7-2)") (class "Default")
      (node (ref "R7") (pin "P$2") (pinfunction "2_P$2") (pintype "passive"))
      (node (ref "U$2") (pin "19") (pinfunction "PPM2_19") (pintype "bidirectional"))
    )
    (net (code "51") (name "Net-(R708-2)") (class "Default")
      (node (ref "LED702") (pin "C") (pinfunction "C_C") (pintype "passive"))
      (node (ref "R708") (pin "P$2") (pinfunction "2_P$2") (pintype "passive"))
    )
    (net (code "52") (name "Net-(R709-2)") (class "Default")
      (node (ref "R709") (pin "P$2") (pinfunction "2_P$2") (pintype "passive"))
      (node (ref "R736") (pin "P$1") (pinfunction "1_P$1") (pintype "passive"))
    )
    (net (code "53") (name "Net-(R712-2)") (class "Default")
      (node (ref "LED705") (pin "C") (pinfunction "C_C") (pintype "passive"))
      (node (ref "R712") (pin "P$2") (pinfunction "2_P$2") (pintype "passive"))
    )
    (net (code "54") (name "Net-(R736-2)") (class "Default")
      (node (ref "LED703") (pin "C") (pinfunction "C_C") (pintype "passive"))
      (node (ref "R736") (pin "P$2") (pinfunction "2_P$2") (pintype "passive"))
    )
    (net (code "55") (name "Net-(R802-1)") (class "Default")
      (node (ref "R802") (pin "P$1") (pinfunction "1_P$1") (pintype "passive"))
      (node (ref "U801") (pin "20") (pinfunction "PB2_20") (pintype "bidirectional"))
    )
    (net (code "56") (name "Net-(R901-2)") (class "Default")
      (node (ref "D902") (pin "C") (pinfunction "C_C") (pintype "passive"))
      (node (ref "R901") (pin "P$2") (pinfunction "2_P$2") (pintype "passive"))
      (node (ref "R910") (pin "P$1") (pinfunction "1_P$1") (pintype "passive"))
      (node (ref "U903") (pin "3") (pinfunction "2Y_3") (pintype "bidirectional"))
    )
    (net (code "57") (name "Net-(R905-1)") (class "Default")
      (node (ref "R905") (pin "P$1") (pinfunction "1_P$1") (pintype "passive"))
      (node (ref "U902") (pin "20") (pinfunction "B1_20") (pintype "bidirectional"))
    )
    (net (code "58") (name "Net-(R905-2)") (class "Default")
      (node (ref "R905") (pin "P$2") (pinfunction "2_P$2") (pintype "passive"))
      (node (ref "U$1") (pin "1") (pinfunction "PPM8_1") (pintype "bidirectional"))
    )
    (net (code "59") (name "Net-(R906-1)") (class "Default")
      (node (ref "R906") (pin "P$1") (pinfunction "1_P$1") (pintype "passive"))
      (node (ref "U902") (pin "17") (pinfunction "B3_17") (pintype "bidirectional"))
    )
    (net (code "60") (name "Net-(R906-2)") (class "Default")
      (node (ref "R906") (pin "P$2") (pinfunction "2_P$2") (pintype "passive"))
      (node (ref "U$1") (pin "7") (pinfunction "PPM6_7") (pintype "bidirectional"))
    )
    (net (code "61") (name "Net-(R907-1)") (class "Default")
      (node (ref "R907") (pin "P$1") (pinfunction "1_P$1") (pintype "passive"))
      (node (ref "U902") (pin "15") (pinfunction "B5_15") (pintype "bidirectional"))
    )
    (net (code "62") (name "Net-(R907-2)") (class "Default")
      (node (ref "R907") (pin "P$2") (pinfunction "2_P$2") (pintype "passive"))
      (node (ref "U$1") (pin "13") (pinfunction "PPM4_13") (pintype "bidirectional"))
    )
    (net (code "63") (name "Net-(R908-1)") (class "Default")
      (node (ref "R908") (pin "P$1") (pinfunction "1_P$1") (pintype "passive"))
      (node (ref "U902") (pin "13") (pinfunction "B7_13") (pintype "bidirectional"))
    )
    (net (code "64") (name "Net-(R908-2)") (class "Default")
      (node (ref "R908") (pin "P$2") (pinfunction "2_P$2") (pintype "passive"))
      (node (ref "U$1") (pin "19") (pinfunction "PPM2_19") (pintype "bidirectional"))
    )
    (net (code "65") (name "Net-(R909-2)") (class "Default")
      (node (ref "JP3") (pin "2") (pinfunction "2_2") (pintype "passive"))
      (node (ref "R909") (pin "P$2") (pinfunction "2_P$2") (pintype "passive"))
    )
    (net (code "66") (name "Net-(R910-2)") (class "Default")
      (node (ref "JP3") (pin "1") (pinfunction "1_1") (pintype "passive"))
      (node (ref "R910") (pin "P$2") (pinfunction "2_P$2") (pintype "passive"))
    )
    (net (code "67") (name "Net-(R914-1)") (class "Default")
      (node (ref "R914") (pin "P$1") (pinfunction "1_P$1") (pintype "passive"))
      (node (ref "U902") (pin "18") (pinfunction "B2_18") (pintype "bidirectional"))
    )
    (net (code "68") (name "Net-(R914-2)") (class "Default")
      (node (ref "R914") (pin "P$2") (pinfunction "2_P$2") (pintype "passive"))
      (node (ref "U$1") (pin "4") (pinfunction "PPM7_4") (pintype "bidirectional"))
    )
    (net (code "69") (name "Net-(R915-1)") (class "Default")
      (node (ref "R915") (pin "P$1") (pinfunction "1_P$1") (pintype "passive"))
      (node (ref "U902") (pin "16") (pinfunction "B4_16") (pintype "bidirectional"))
    )
    (net (code "70") (name "Net-(R915-2)") (class "Default")
      (node (ref "R915") (pin "P$2") (pinfunction "2_P$2") (pintype "passive"))
      (node (ref "U$1") (pin "10") (pinfunction "PPM5_10") (pintype "bidirectional"))
    )
    (net (code "71") (name "Net-(R916-1)") (class "Default")
      (node (ref "R916") (pin "P$1") (pinfunction "1_P$1") (pintype "passive"))
      (node (ref "U902") (pin "14") (pinfunction "B6_14") (pintype "bidirectional"))
    )
    (net (code "72") (name "Net-(R916-2)") (class "Default")
      (node (ref "R916") (pin "P$2") (pinfunction "2_P$2") (pintype "passive"))
      (node (ref "U$1") (pin "16") (pinfunction "PPM3_16") (pintype "bidirectional"))
    )
    (net (code "73") (name "Net-(R918-2)") (class "Default")
      (node (ref "R918") (pin "P$2") (pinfunction "2_P$2") (pintype "passive"))
      (node (ref "R922") (pin "P$1") (pinfunction "1_P$1") (pintype "passive"))
    )
    (net (code "74") (name "Net-(R1001-2)") (class "Default")
      (node (ref "R1001") (pin "P$2") (pinfunction "2_P$2") (pintype "passive"))
      (node (ref "U1001") (pin "7") (pinfunction "ILIM_7") (pintype "bidirectional"))
    )
    (net (code "75") (name "Net-(U1001-IN)") (class "Default")
      (node (ref "L901") (pin "P$2") (pinfunction "P$2_P$2") (pintype "bidirectional"))
      (node (ref "U1001") (pin "1") (pinfunction "IN_1") (pintype "bidirectional"))
    )
    (net (code "76") (name "OUT_CH1") (class "Default")
      (node (ref "U801") (pin "18") (pinfunction "PB0_18") (pintype "bidirectional"))
      (node (ref "U902") (pin "1") (pinfunction "A1_1") (pintype "bidirectional"))
    )
    (net (code "77") (name "OUT_CH2") (class "Default")
      (node (ref "U801") (pin "19") (pinfunction "PB1_19") (pintype "bidirectional"))
      (node (ref "U902") (pin "3") (pinfunction "A2_3") (pintype "bidirectional"))
    )
    (net (code "78") (name "OUT_CH3") (class "Default")
      (node (ref "U801") (pin "39") (pinfunction "PB3_39") (pintype "bidirectional"))
      (node (ref "U902") (pin "4") (pinfunction "A3_4") (pintype "bidirectional"))
    )
    (net (code "79") (name "OUT_CH4") (class "Default")
      (node (ref "U801") (pin "42") (pinfunction "PB6_42") (pintype "bidirectional"))
      (node (ref "U902") (pin "5") (pinfunction "A4_5") (pintype "bidirectional"))
    )
    (net (code "80") (name "OUT_CH5") (class "Default")
      (node (ref "U801") (pin "43") (pinfunction "PB7_43") (pintype "bidirectional"))
      (node (ref "U902") (pin "6") (pinfunction "A5_6") (pintype "bidirectional"))
    )
    (net (code "81") (name "OUT_CH6") (class "Default")
      (node (ref "U801") (pin "45") (pinfunction "PB8_45") (pintype "bidirectional"))
      (node (ref "U902") (pin "7") (pinfunction "A6_7") (pintype "bidirectional"))
    )
    (net (code "82") (name "OUT_CH7") (class "Default")
      (node (ref "U801") (pin "46") (pinfunction "PB9_46") (pintype "bidirectional"))
      (node (ref "U902") (pin "8") (pinfunction "A7_8") (pintype "bidirectional"))
    )
    (net (code "83") (name "RSSI_IN") (class "Default")
      (node (ref "R901") (pin "P$1") (pinfunction "1_P$1") (pintype "passive"))
      (node (ref "U801") (pin "15") (pinfunction "PA5_15") (pintype "bidirectional"))
    )
    (net (code "84") (name "SBUS_INPUT") (class "Default")
      (node (ref "U801") (pin "41") (pinfunction "PB5_41") (pintype "bidirectional"))
      (node (ref "U903") (pin "6") (pinfunction "1Y_6") (pintype "bidirectional"))
    )
    (net (code "85") (name "SBUS_OUTPUT") (class "Default")
      (node (ref "U801") (pin "40") (pinfunction "PB4_40") (pintype "bidirectional"))
      (node (ref "U903") (pin "5") (pinfunction "2A_5") (pintype "bidirectional"))
    )
    (net (code "86") (name "SCK2") (class "Default")
      (node (ref "JP2") (pin "4") (pinfunction "4_4") (pintype "passive"))
      (node (ref "U801") (pin "26") (pinfunction "PB13_26") (pintype "bidirectional"))
    )
    (net (code "87") (name "VBAT") (class "Default")
      (node (ref "U801") (pin "1") (pinfunction "VBAT_1") (pintype "power_in"))
    )
    (net (code "88") (name "VBUS") (class "Default")
      (node (ref "J301") (pin "VBUS") (pinfunction "1_VBUS") (pintype "power_in"))
      (node (ref "U302") (pin "5") (pinfunction "VBUS_5") (pintype "bidirectional"))
    )
    (net (code "89") (name "VDD_3V3_SPEKTRUM") (class "Default")
      (node (ref "C1008") (pin "P$1") (pinfunction "1_P$1") (pintype "passive"))
      (node (ref "D801") (pin "C") (pinfunction "C_C") (pintype "passive"))
      (node (ref "J801") (pin "P$1") (pinfunction "P$1_P$1") (pintype "bidirectional"))
      (node (ref "U1002") (pin "8") (pinfunction "VOUT1_8") (pintype "bidirectional"))
    )
    (net (code "90") (name "VDD_3V3_SPEKTRUM_EN") (class "Default")
      (node (ref "R1002") (pin "P$2") (pinfunction "2_P$2") (pintype "passive"))
      (node (ref "U1002") (pin "5") (pinfunction "EN1_5") (pintype "bidirectional"))
      (node (ref "U801") (pin "2") (pinfunction "PC13_2") (pintype "bidirectional"))
    )
    (net (code "91") (name "VDD_5V_IN") (class "Default")
      (node (ref "D904") (pin "ANODE") (pinfunction "A_ANODE") (pintype "passive"))
      (node (ref "F1001") (pin "1") (pinfunction "1_1") (pintype "bidirectional"))
      (node (ref "JP3") (pin "4") (pinfunction "4_4") (pintype "passive"))
      (node (ref "R922") (pin "P$2") (pinfunction "2_P$2") (pintype "passive"))
      (node (ref "U$1") (pin "11") (pinfunction "+5V_11") (pintype "bidirectional"))
      (node (ref "U$1") (pin "14") (pinfunction "+5V_14") (pintype "bidirectional"))
      (node (ref "U$1") (pin "17") (pinfunction "+5V_17") (pintype "bidirectional"))
      (node (ref "U$1") (pin "2") (pinfunction "+5V_2") (pintype "bidirectional"))
      (node (ref "U$1") (pin "20") (pinfunction "+5V_20") (pintype "bidirectional"))
      (node (ref "U$1") (pin "23") (pinfunction "+5V_23") (pintype "bidirectional"))
      (node (ref "U$1") (pin "5") (pinfunction "+5V_5") (pintype "bidirectional"))
      (node (ref "U$1") (pin "8") (pinfunction "+5V_8") (pintype "bidirectional"))
      (node (ref "U$2") (pin "11") (pinfunction "+5V_11") (pintype "bidirectional"))
      (node (ref "U$2") (pin "14") (pinfunction "+5V_14") (pintype "bidirectional"))
      (node (ref "U$2") (pin "17") (pinfunction "+5V_17") (pintype "bidirectional"))
      (node (ref "U$2") (pin "2") (pinfunction "+5V_2") (pintype "bidirectional"))
      (node (ref "U$2") (pin "20") (pinfunction "+5V_20") (pintype "bidirectional"))
      (node (ref "U$2") (pin "23") (pinfunction "+5V_23") (pintype "bidirectional"))
      (node (ref "U$2") (pin "5") (pinfunction "+5V_5") (pintype "bidirectional"))
      (node (ref "U$2") (pin "8") (pinfunction "+5V_8") (pintype "bidirectional"))
    )
    (net (code "92") (name "VDD_SERVO_SENS") (class "Default")
      (node (ref "R918") (pin "P$1") (pinfunction "1_P$1") (pintype "passive"))
      (node (ref "R919") (pin "P$2") (pinfunction "2_P$2") (pintype "passive"))
      (node (ref "U801") (pin "14") (pinfunction "PA4_14") (pintype "bidirectional"))
    )
    (net (code "93") (name "unconnected-(J301-4-PadID)") (class "Default")
      (node (ref "J301") (pin "ID") (pinfunction "4_ID") (pintype "passive"))
    )
    (net (code "94") (name "unconnected-(JX802A-S-Pad10)") (class "Default")
      (node (ref "JX802") (pin "10") (pinfunction "S_10") (pintype "passive"))
    )
    (net (code "95") (name "unconnected-(JX802F-S-Pad8)") (class "Default")
      (node (ref "JX802") (pin "8") (pinfunction "S_8") (pintype "passive"))
    )
    (net (code "96") (name "unconnected-(JX802G-S-Pad6)") (class "Default")
      (node (ref "JX802") (pin "6") (pinfunction "S_6") (pintype "passive"))
    )
    (net (code "97") (name "unconnected-(U$1-PPM1-Pad22)") (class "Default")
      (node (ref "U$1") (pin "22") (pinfunction "PPM1_22") (pintype "bidirectional"))
    )
    (net (code "98") (name "unconnected-(U$2-PPM1-Pad22)") (class "Default")
      (node (ref "U$2") (pin "22") (pinfunction "PPM1_22") (pintype "bidirectional"))
    )
    (net (code "99") (name "unconnected-(U1-A8-Pad9)") (class "Default")
      (node (ref "U1") (pin "9") (pinfunction "A8_9") (pintype "bidirectional"))
    )
    (net (code "100") (name "unconnected-(U1-B8-Pad12)") (class "Default")
      (node (ref "U1") (pin "12") (pinfunction "B8_12") (pintype "bidirectional"))
    )
    (net (code "101") (name "unconnected-(U902-A8-Pad9)") (class "Default")
      (node (ref "U902") (pin "9") (pinfunction "A8_9") (pintype "bidirectional"))
    )
    (net (code "102") (name "unconnected-(U902-B8-Pad12)") (class "Default")
      (node (ref "U902") (pin "12") (pinfunction "B8_12") (pintype "bidirectional"))
    )
  )
)
